# adb.net
KiCad netlist of a schematic drawn in EAGLE
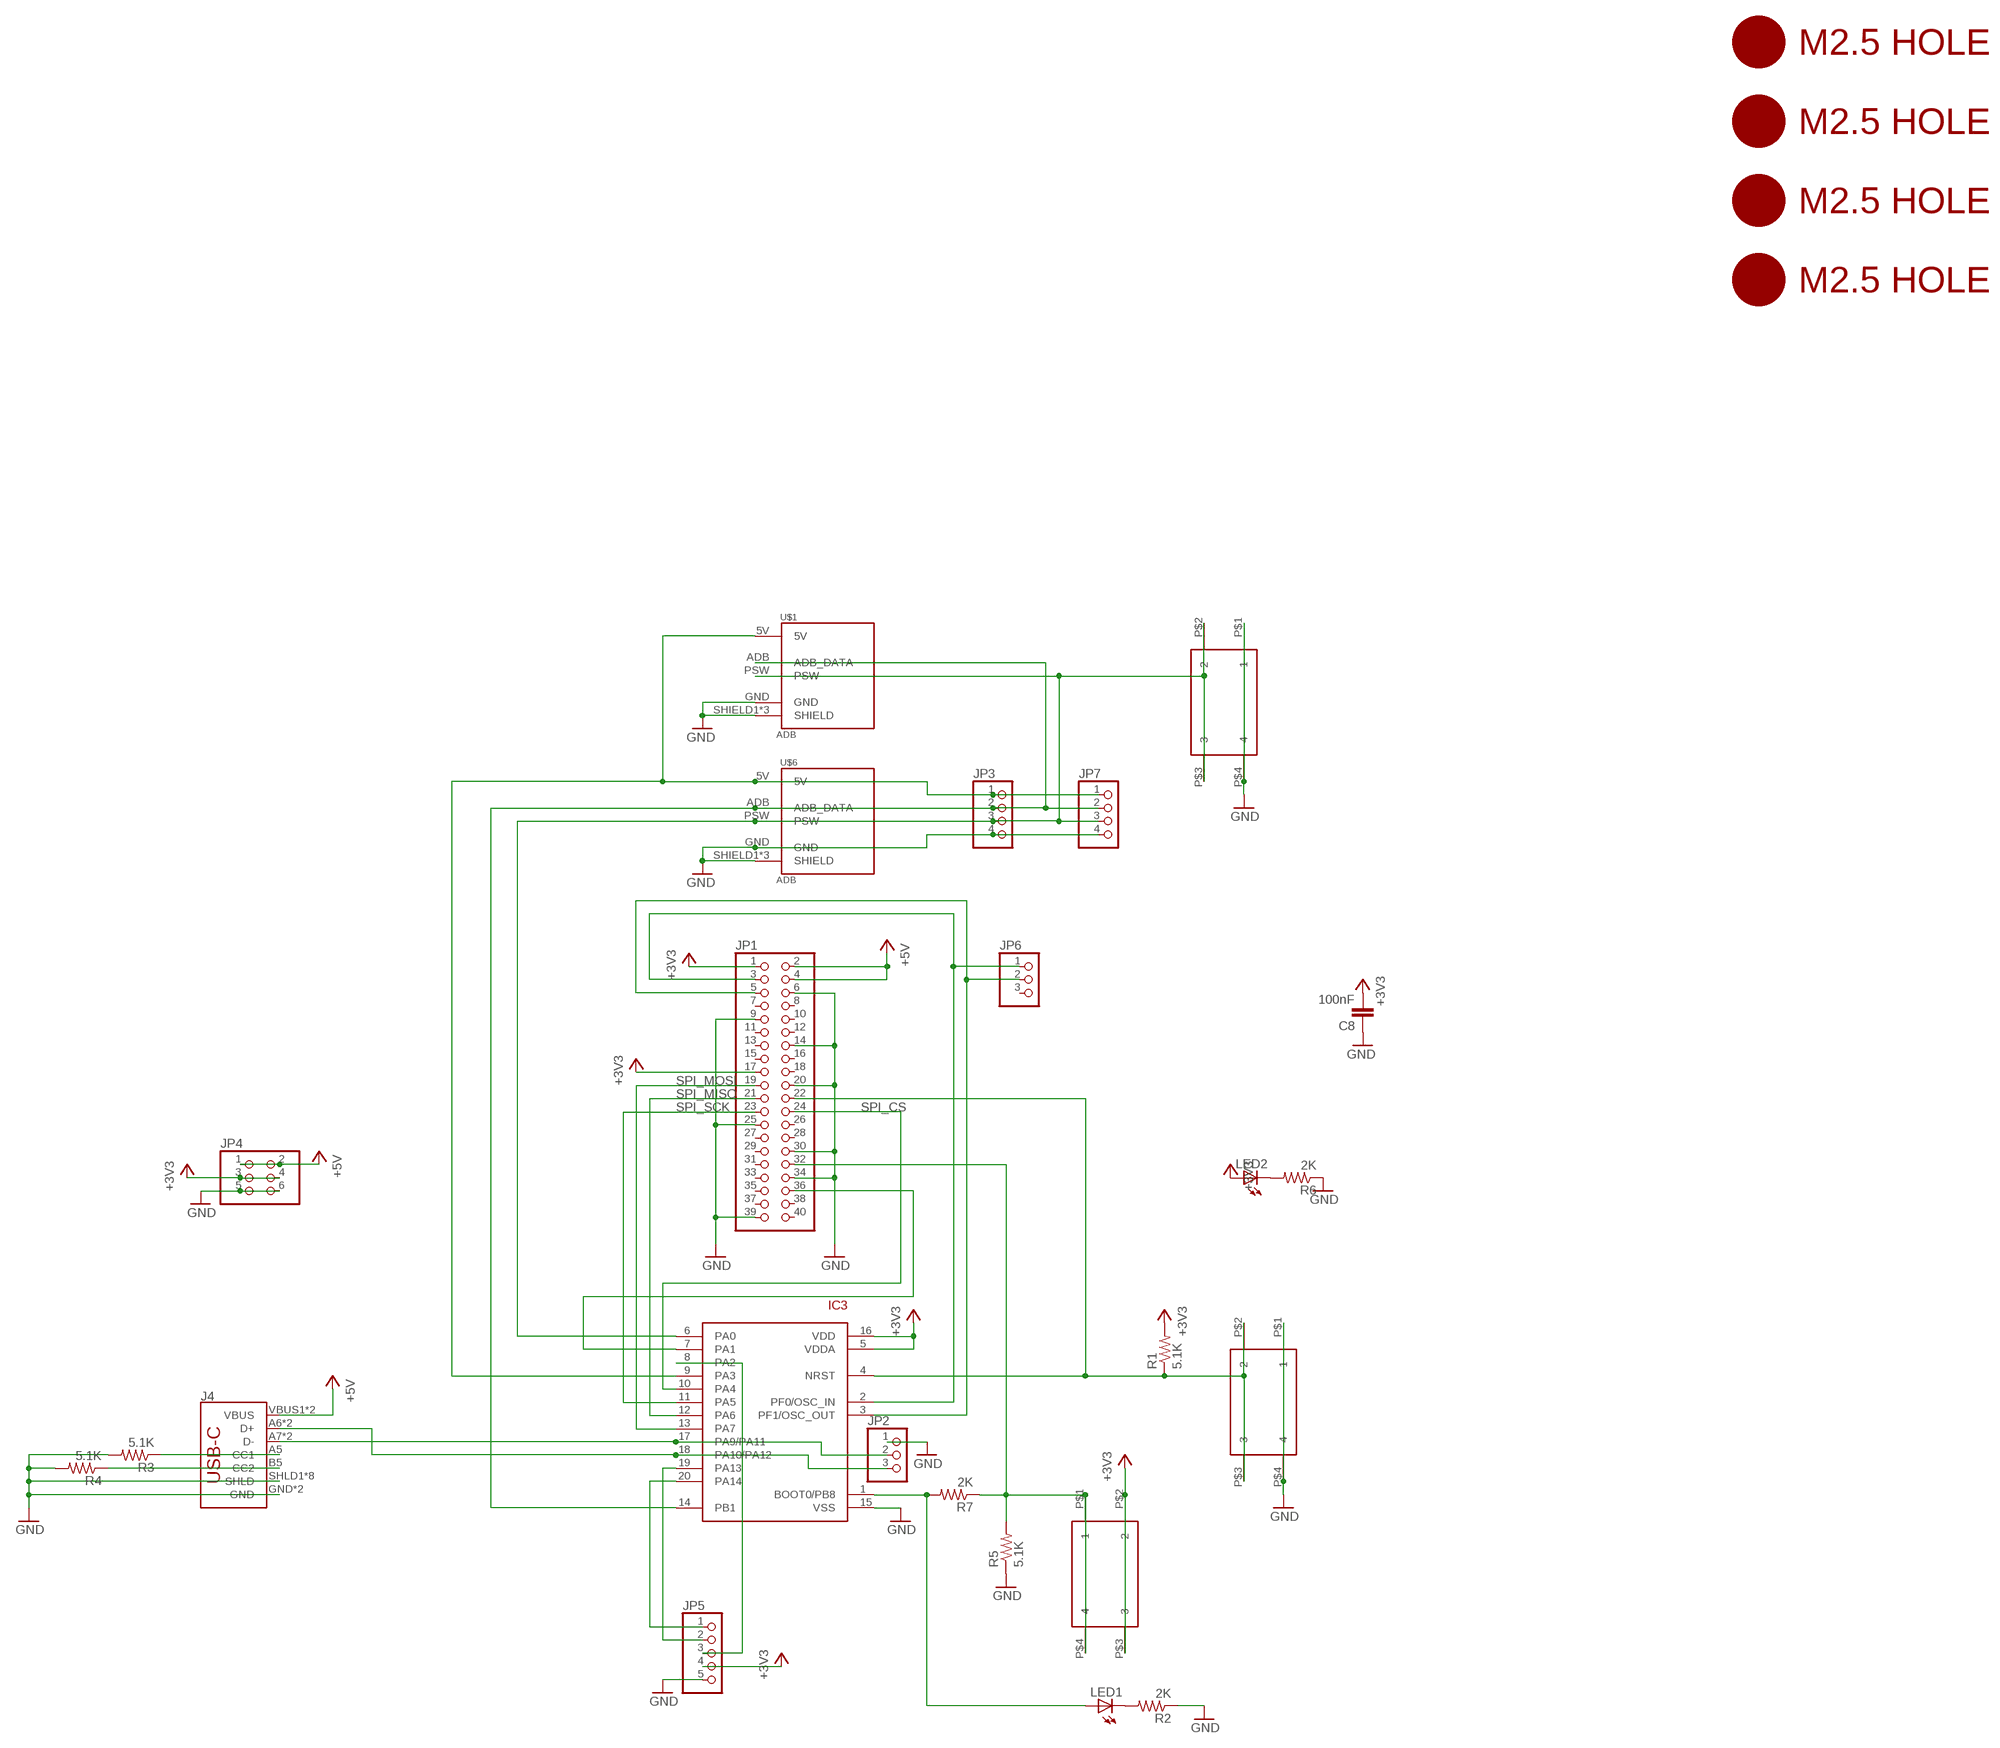
[diagram p0: schematic, sheet 1]

(export (version "E")
  (design (tool "Eeschema 10.0.6"))
  (components
    (comp (ref "C8")
      (value "100nF")
      (footprint "eagle-import:0805@1")
      (libsource (lib "eagle-import") (part "CAP0805"))
    )
    (comp (ref "IC3")
      (value "STM32F042F4")
      (footprint "eagle-import:TSSOP20")
      (libsource (lib "eagle-import") (part "STM32F042F4"))
    )
    (comp (ref "J4")
      (value "USB_C16PIN")
      (footprint "eagle-import:USB-C-16P")
      (libsource (lib "eagle-import") (part "USB_C16PIN"))
    )
    (comp (ref "JP1")
      (value "PINHD-2X20-BIG")
      (footprint "eagle-import:2X20-BIG")
      (libsource (lib "eagle-import") (part "PINHD-2X20-BIG"))
    )
    (comp (ref "JP2")
      (value "PINHD-1X3")
      (footprint "eagle-import:1X03")
      (libsource (lib "eagle-import") (part "PINHD-1X3"))
    )
    (comp (ref "JP3")
      (value "PINHD-1X4")
      (footprint "eagle-import:1X04")
      (libsource (lib "eagle-import") (part "PINHD-1X4"))
    )
    (comp (ref "JP4")
      (value "PINHD-2X3")
      (footprint "eagle-import:2X03")
      (libsource (lib "eagle-import") (part "PINHD-2X3"))
    )
    (comp (ref "JP5")
      (value "PINHD-1X5")
      (footprint "eagle-import:1X05")
      (libsource (lib "eagle-import") (part "PINHD-1X5"))
    )
    (comp (ref "JP6")
      (value "PINHD-1X3")
      (footprint "eagle-import:1X03")
      (libsource (lib "eagle-import") (part "PINHD-1X3"))
    )
    (comp (ref "JP7")
      (value "PINHD-1X4")
      (footprint "eagle-import:1X04")
      (libsource (lib "eagle-import") (part "PINHD-1X4"))
    )
    (comp (ref "LED1")
      (value "LEDCHIP-LED0805")
      (footprint "eagle-import:CHIP-LED0805")
      (libsource (lib "eagle-import") (part "LEDCHIP-LED0805"))
    )
    (comp (ref "LED2")
      (value "LEDCHIP-LED0805")
      (footprint "eagle-import:CHIP-LED0805")
      (libsource (lib "eagle-import") (part "LEDCHIP-LED0805"))
    )
    (comp (ref "R1")
      (value "5.1K")
      (footprint "eagle-import:0805")
      (libsource (lib "eagle-import") (part "RESISTOR0805-RES"))
    )
    (comp (ref "R2")
      (value "2K")
      (footprint "eagle-import:0805")
      (libsource (lib "eagle-import") (part "RESISTOR0805-RES"))
    )
    (comp (ref "R3")
      (value "5.1K")
      (footprint "eagle-import:0805")
      (libsource (lib "eagle-import") (part "RESISTOR0805-RES"))
    )
    (comp (ref "R4")
      (value "5.1K")
      (footprint "eagle-import:0805")
      (libsource (lib "eagle-import") (part "RESISTOR0805-RES"))
    )
    (comp (ref "R5")
      (value "5.1K")
      (footprint "eagle-import:0805")
      (libsource (lib "eagle-import") (part "RESISTOR0805-RES"))
    )
    (comp (ref "R6")
      (value "2K")
      (footprint "eagle-import:0805")
      (libsource (lib "eagle-import") (part "RESISTOR0805-RES"))
    )
    (comp (ref "R7")
      (value "2K")
      (footprint "eagle-import:0805")
      (libsource (lib "eagle-import") (part "RESISTOR0805-RES"))
    )
    (comp (ref "SW1")
      (value "324_SW")
      (footprint "eagle-import:342_SWICH_FOOT")
      (libsource (lib "eagle-import") (part "324_SW"))
    )
    (comp (ref "SW2")
      (value "324_SW")
      (footprint "eagle-import:342_SWICH_FOOT")
      (libsource (lib "eagle-import") (part "324_SW"))
    )
    (comp (ref "SW4")
      (value "324_SW")
      (footprint "eagle-import:342_SWICH_FOOT")
      (libsource (lib "eagle-import") (part "324_SW"))
    )
    (comp (ref "U$1")
      (value "ADB")
      (footprint "eagle-import:DIN4")
      (libsource (lib "eagle-import") (part "ADB"))
    )
    (comp (ref "U$2")
      (value "M2.5HOLE")
      (footprint "eagle-import:M2.5HOLE")
      (libsource (lib "eagle-import") (part "M2.5HOLE"))
    )
    (comp (ref "U$3")
      (value "M2.5HOLE")
      (footprint "eagle-import:M2.5HOLE")
      (libsource (lib "eagle-import") (part "M2.5HOLE"))
    )
    (comp (ref "U$4")
      (value "M2.5HOLE")
      (footprint "eagle-import:M2.5HOLE")
      (libsource (lib "eagle-import") (part "M2.5HOLE"))
    )
    (comp (ref "U$5")
      (value "M2.5HOLE")
      (footprint "eagle-import:M2.5HOLE")
      (libsource (lib "eagle-import") (part "M2.5HOLE"))
    )
    (comp (ref "U$6")
      (value "ADB")
      (footprint "eagle-import:DIN4")
      (libsource (lib "eagle-import") (part "ADB"))
    )
  )
  (nets
    (net (code "1") (name "+3V3") (class "Default")
      (node (ref "C8") (pin "2") (pinfunction "2_2") (pintype "passive"))
      (node (ref "IC3") (pin "16") (pinfunction "VDD_16") (pintype "bidirectional"))
      (node (ref "IC3") (pin "5") (pinfunction "VDDA_5") (pintype "bidirectional"))
      (node (ref "JP1") (pin "1") (pinfunction "1_1") (pintype "passive"))
      (node (ref "JP1") (pin "17") (pinfunction "17_17") (pintype "passive"))
      (node (ref "JP4") (pin "3") (pinfunction "3_3") (pintype "passive"))
      (node (ref "JP4") (pin "4") (pinfunction "4_4") (pintype "passive"))
      (node (ref "JP5") (pin "4") (pinfunction "4_4") (pintype "passive"))
      (node (ref "LED2") (pin "A") (pinfunction "A_A") (pintype "passive"))
      (node (ref "R1") (pin "2") (pinfunction "2_2") (pintype "passive"))
      (node (ref "SW1") (pin "P$2") (pinfunction "2_P$2") (pintype "bidirectional"))
      (node (ref "SW1") (pin "P$3") (pinfunction "3_P$3") (pintype "bidirectional"))
    )
    (net (code "2") (name "+5V") (class "Default")
      (node (ref "J4") (pin "VBUS1") (pinfunction "VBUS_VBUS1") (pintype "bidirectional"))
      (node (ref "J4") (pin "VBUS2") (pinfunction "VBUS_VBUS2") (pintype "bidirectional"))
      (node (ref "JP1") (pin "2") (pinfunction "2_2") (pintype "passive"))
      (node (ref "JP1") (pin "4") (pinfunction "4_4") (pintype "passive"))
      (node (ref "JP4") (pin "1") (pinfunction "1_1") (pintype "passive"))
      (node (ref "JP4") (pin "2") (pinfunction "2_2") (pintype "passive"))
    )
    (net (code "3") (name "/SPI_CS") (class "Default")
      (node (ref "IC3") (pin "10") (pinfunction "PA4_10") (pintype "bidirectional"))
      (node (ref "JP1") (pin "24") (pinfunction "24_24") (pintype "passive"))
    )
    (net (code "4") (name "/SPI_MISO") (class "Default")
      (node (ref "IC3") (pin "12") (pinfunction "PA6_12") (pintype "bidirectional"))
      (node (ref "JP1") (pin "21") (pinfunction "21_21") (pintype "passive"))
    )
    (net (code "5") (name "/SPI_MOSI") (class "Default")
      (node (ref "IC3") (pin "13") (pinfunction "PA7_13") (pintype "bidirectional"))
      (node (ref "JP1") (pin "19") (pinfunction "19_19") (pintype "passive"))
    )
    (net (code "6") (name "/SPI_SCK") (class "Default")
      (node (ref "IC3") (pin "11") (pinfunction "PA5_11") (pintype "bidirectional"))
      (node (ref "JP1") (pin "23") (pinfunction "23_23") (pintype "passive"))
    )
    (net (code "7") (name "GND") (class "Default")
      (node (ref "C8") (pin "1") (pinfunction "1_1") (pintype "passive"))
      (node (ref "IC3") (pin "15") (pinfunction "VSS_15") (pintype "bidirectional"))
      (node (ref "J4") (pin "GND") (pinfunction "GND_GND") (pintype "bidirectional"))
      (node (ref "J4") (pin "GND2") (pinfunction "GND_GND2") (pintype "bidirectional"))
      (node (ref "J4") (pin "SHLD1") (pinfunction "SHLD_SHLD1") (pintype "bidirectional"))
      (node (ref "J4") (pin "SHLD2") (pinfunction "SHLD_SHLD2") (pintype "bidirectional"))
      (node (ref "J4") (pin "SHLD3") (pinfunction "SHLD_SHLD3") (pintype "bidirectional"))
      (node (ref "J4") (pin "SHLD4") (pinfunction "SHLD_SHLD4") (pintype "bidirectional"))
      (node (ref "J4") (pin "SHLD5") (pinfunction "SHLD_SHLD5") (pintype "bidirectional"))
      (node (ref "J4") (pin "SHLD6") (pinfunction "SHLD_SHLD6") (pintype "bidirectional"))
      (node (ref "J4") (pin "SHLD7") (pinfunction "SHLD_SHLD7") (pintype "bidirectional"))
      (node (ref "J4") (pin "SHLD8") (pinfunction "SHLD_SHLD8") (pintype "bidirectional"))
      (node (ref "JP1") (pin "14") (pinfunction "14_14") (pintype "passive"))
      (node (ref "JP1") (pin "20") (pinfunction "20_20") (pintype "passive"))
      (node (ref "JP1") (pin "25") (pinfunction "25_25") (pintype "passive"))
      (node (ref "JP1") (pin "30") (pinfunction "30_30") (pintype "passive"))
      (node (ref "JP1") (pin "34") (pinfunction "34_34") (pintype "passive"))
      (node (ref "JP1") (pin "39") (pinfunction "39_39") (pintype "passive"))
      (node (ref "JP1") (pin "6") (pinfunction "6_6") (pintype "passive"))
      (node (ref "JP1") (pin "9") (pinfunction "9_9") (pintype "passive"))
      (node (ref "JP2") (pin "1") (pinfunction "1_1") (pintype "passive"))
      (node (ref "JP3") (pin "4") (pinfunction "4_4") (pintype "passive"))
      (node (ref "JP4") (pin "5") (pinfunction "5_5") (pintype "passive"))
      (node (ref "JP4") (pin "6") (pinfunction "6_6") (pintype "passive"))
      (node (ref "JP5") (pin "5") (pinfunction "5_5") (pintype "passive"))
      (node (ref "JP7") (pin "4") (pinfunction "4_4") (pintype "passive"))
      (node (ref "R2") (pin "1") (pinfunction "1_1") (pintype "passive"))
      (node (ref "R3") (pin "2") (pinfunction "2_2") (pintype "passive"))
      (node (ref "R4") (pin "2") (pinfunction "2_2") (pintype "passive"))
      (node (ref "R5") (pin "1") (pinfunction "1_1") (pintype "passive"))
      (node (ref "R6") (pin "1") (pinfunction "1_1") (pintype "passive"))
      (node (ref "SW2") (pin "P$1") (pinfunction "1_P$1") (pintype "bidirectional"))
      (node (ref "SW2") (pin "P$4") (pinfunction "4_P$4") (pintype "bidirectional"))
      (node (ref "SW4") (pin "P$1") (pinfunction "1_P$1") (pintype "bidirectional"))
      (node (ref "SW4") (pin "P$4") (pinfunction "4_P$4") (pintype "bidirectional"))
      (node (ref "U$1") (pin "GND") (pinfunction "GND_GND") (pintype "bidirectional"))
      (node (ref "U$1") (pin "SHIELD1") (pinfunction "SHIELD_SHIELD1") (pintype "bidirectional"))
      (node (ref "U$1") (pin "SHIELD2") (pinfunction "SHIELD_SHIELD2") (pintype "bidirectional"))
      (node (ref "U$1") (pin "SHIELD3") (pinfunction "SHIELD_SHIELD3") (pintype "bidirectional"))
      (node (ref "U$6") (pin "GND") (pinfunction "GND_GND") (pintype "bidirectional"))
      (node (ref "U$6") (pin "SHIELD1") (pinfunction "SHIELD_SHIELD1") (pintype "bidirectional"))
      (node (ref "U$6") (pin "SHIELD2") (pinfunction "SHIELD_SHIELD2") (pintype "bidirectional"))
      (node (ref "U$6") (pin "SHIELD3") (pinfunction "SHIELD_SHIELD3") (pintype "bidirectional"))
    )
    (net (code "8") (name "Net-(IC3-BOOT0{slash}PB8)") (class "Default")
      (node (ref "IC3") (pin "1") (pinfunction "BOOT0/PB8_1") (pintype "bidirectional"))
      (node (ref "LED1") (pin "A") (pinfunction "A_A") (pintype "passive"))
      (node (ref "R7") (pin "2") (pinfunction "2_2") (pintype "passive"))
    )
    (net (code "9") (name "Net-(IC3-NRST)") (class "Default")
      (node (ref "IC3") (pin "4") (pinfunction "NRST_4") (pintype "bidirectional"))
      (node (ref "JP1") (pin "22") (pinfunction "22_22") (pintype "passive"))
      (node (ref "R1") (pin "1") (pinfunction "1_1") (pintype "passive"))
      (node (ref "SW4") (pin "P$2") (pinfunction "2_P$2") (pintype "bidirectional"))
      (node (ref "SW4") (pin "P$3") (pinfunction "3_P$3") (pintype "bidirectional"))
    )
    (net (code "10") (name "Net-(IC3-PA0)") (class "Default")
      (node (ref "IC3") (pin "6") (pinfunction "PA0_6") (pintype "bidirectional"))
      (node (ref "JP3") (pin "3") (pinfunction "3_3") (pintype "passive"))
      (node (ref "JP7") (pin "3") (pinfunction "3_3") (pintype "passive"))
      (node (ref "SW2") (pin "P$2") (pinfunction "2_P$2") (pintype "bidirectional"))
      (node (ref "SW2") (pin "P$3") (pinfunction "3_P$3") (pintype "bidirectional"))
      (node (ref "U$1") (pin "PSW") (pinfunction "PSW_PSW") (pintype "bidirectional"))
      (node (ref "U$6") (pin "PSW") (pinfunction "PSW_PSW") (pintype "bidirectional"))
    )
    (net (code "11") (name "Net-(IC3-PA1)") (class "Default")
      (node (ref "IC3") (pin "7") (pinfunction "PA1_7") (pintype "bidirectional"))
      (node (ref "JP1") (pin "36") (pinfunction "36_36") (pintype "passive"))
    )
    (net (code "12") (name "Net-(IC3-PA2)") (class "Default")
      (node (ref "IC3") (pin "8") (pinfunction "PA2_8") (pintype "bidirectional"))
      (node (ref "JP5") (pin "3") (pinfunction "3_3") (pintype "passive"))
    )
    (net (code "13") (name "Net-(IC3-PA3)") (class "Default")
      (node (ref "IC3") (pin "9") (pinfunction "PA3_9") (pintype "bidirectional"))
      (node (ref "JP3") (pin "1") (pinfunction "1_1") (pintype "passive"))
      (node (ref "JP7") (pin "1") (pinfunction "1_1") (pintype "passive"))
      (node (ref "U$1") (pin "5V") (pinfunction "5V_5V") (pintype "bidirectional"))
      (node (ref "U$6") (pin "5V") (pinfunction "5V_5V") (pintype "bidirectional"))
    )
    (net (code "14") (name "Net-(IC3-PA9{slash}PA11)") (class "Default")
      (node (ref "IC3") (pin "17") (pinfunction "PA9/PA11_17") (pintype "bidirectional"))
      (node (ref "J4") (pin "A7") (pinfunction "D-_A7") (pintype "bidirectional"))
      (node (ref "J4") (pin "B7") (pinfunction "D-_B7") (pintype "bidirectional"))
      (node (ref "JP2") (pin "2") (pinfunction "2_2") (pintype "passive"))
    )
    (net (code "15") (name "Net-(IC3-PA10{slash}PA12)") (class "Default")
      (node (ref "IC3") (pin "18") (pinfunction "PA10/PA12_18") (pintype "bidirectional"))
      (node (ref "J4") (pin "A6") (pinfunction "D+_A6") (pintype "bidirectional"))
      (node (ref "J4") (pin "B6") (pinfunction "D+_B6") (pintype "bidirectional"))
      (node (ref "JP2") (pin "3") (pinfunction "3_3") (pintype "passive"))
    )
    (net (code "16") (name "Net-(IC3-PA13)") (class "Default")
      (node (ref "IC3") (pin "19") (pinfunction "PA13_19") (pintype "bidirectional"))
      (node (ref "JP5") (pin "2") (pinfunction "2_2") (pintype "passive"))
    )
    (net (code "17") (name "Net-(IC3-PA14)") (class "Default")
      (node (ref "IC3") (pin "20") (pinfunction "PA14_20") (pintype "bidirectional"))
      (node (ref "JP5") (pin "1") (pinfunction "1_1") (pintype "passive"))
    )
    (net (code "18") (name "Net-(IC3-PB1)") (class "Default")
      (node (ref "IC3") (pin "14") (pinfunction "PB1_14") (pintype "bidirectional"))
      (node (ref "JP3") (pin "2") (pinfunction "2_2") (pintype "passive"))
      (node (ref "JP7") (pin "2") (pinfunction "2_2") (pintype "passive"))
      (node (ref "U$1") (pin "ADB") (pinfunction "ADB_DATA_ADB") (pintype "bidirectional"))
      (node (ref "U$6") (pin "ADB") (pinfunction "ADB_DATA_ADB") (pintype "bidirectional"))
    )
    (net (code "19") (name "Net-(IC3-PF0{slash}OSC_IN)") (class "Default")
      (node (ref "IC3") (pin "2") (pinfunction "PF0/OSC_IN_2") (pintype "bidirectional"))
      (node (ref "JP1") (pin "3") (pinfunction "3_3") (pintype "passive"))
      (node (ref "JP6") (pin "1") (pinfunction "1_1") (pintype "passive"))
    )
    (net (code "20") (name "Net-(IC3-PF1{slash}OSC_OUT)") (class "Default")
      (node (ref "IC3") (pin "3") (pinfunction "PF1/OSC_OUT_3") (pintype "bidirectional"))
      (node (ref "JP1") (pin "5") (pinfunction "5_5") (pintype "passive"))
      (node (ref "JP6") (pin "2") (pinfunction "2_2") (pintype "passive"))
    )
    (net (code "21") (name "Net-(J4-CC1)") (class "Default")
      (node (ref "J4") (pin "A5") (pinfunction "CC1_A5") (pintype "bidirectional"))
      (node (ref "R3") (pin "1") (pinfunction "1_1") (pintype "passive"))
    )
    (net (code "22") (name "Net-(J4-CC2)") (class "Default")
      (node (ref "J4") (pin "B5") (pinfunction "CC2_B5") (pintype "bidirectional"))
      (node (ref "R4") (pin "1") (pinfunction "1_1") (pintype "passive"))
    )
    (net (code "23") (name "Net-(LED1-PadC)") (class "Default")
      (node (ref "LED1") (pin "C") (pinfunction "C_C") (pintype "passive"))
      (node (ref "R2") (pin "2") (pinfunction "2_2") (pintype "passive"))
    )
    (net (code "24") (name "Net-(LED2-PadC)") (class "Default")
      (node (ref "LED2") (pin "C") (pinfunction "C_C") (pintype "passive"))
      (node (ref "R6") (pin "2") (pinfunction "2_2") (pintype "passive"))
    )
    (net (code "25") (name "Net-(SW1-1)") (class "Default")
      (node (ref "JP1") (pin "32") (pinfunction "32_32") (pintype "passive"))
      (node (ref "R5") (pin "2") (pinfunction "2_2") (pintype "passive"))
      (node (ref "R7") (pin "1") (pinfunction "1_1") (pintype "passive"))
      (node (ref "SW1") (pin "P$1") (pinfunction "1_P$1") (pintype "bidirectional"))
      (node (ref "SW1") (pin "P$4") (pinfunction "4_P$4") (pintype "bidirectional"))
    )
    (net (code "26") (name "unconnected-(JP1-Pad7)") (class "Default")
      (node (ref "JP1") (pin "7") (pinfunction "7_7") (pintype "passive"))
    )
    (net (code "27") (name "unconnected-(JP1-Pad8)") (class "Default")
      (node (ref "JP1") (pin "8") (pinfunction "8_8") (pintype "passive"))
    )
    (net (code "28") (name "unconnected-(JP1-Pad10)") (class "Default")
      (node (ref "JP1") (pin "10") (pinfunction "10_10") (pintype "passive"))
    )
    (net (code "29") (name "unconnected-(JP1-Pad11)") (class "Default")
      (node (ref "JP1") (pin "11") (pinfunction "11_11") (pintype "passive"))
    )
    (net (code "30") (name "unconnected-(JP1-Pad12)") (class "Default")
      (node (ref "JP1") (pin "12") (pinfunction "12_12") (pintype "passive"))
    )
    (net (code "31") (name "unconnected-(JP1-Pad13)") (class "Default")
      (node (ref "JP1") (pin "13") (pinfunction "13_13") (pintype "passive"))
    )
    (net (code "32") (name "unconnected-(JP1-Pad15)") (class "Default")
      (node (ref "JP1") (pin "15") (pinfunction "15_15") (pintype "passive"))
    )
    (net (code "33") (name "unconnected-(JP1-Pad16)") (class "Default")
      (node (ref "JP1") (pin "16") (pinfunction "16_16") (pintype "passive"))
    )
    (net (code "34") (name "unconnected-(JP1-Pad18)") (class "Default")
      (node (ref "JP1") (pin "18") (pinfunction "18_18") (pintype "passive"))
    )
    (net (code "35") (name "unconnected-(JP1-Pad26)") (class "Default")
      (node (ref "JP1") (pin "26") (pinfunction "26_26") (pintype "passive"))
    )
    (net (code "36") (name "unconnected-(JP1-Pad27)") (class "Default")
      (node (ref "JP1") (pin "27") (pinfunction "27_27") (pintype "passive"))
    )
    (net (code "37") (name "unconnected-(JP1-Pad28)") (class "Default")
      (node (ref "JP1") (pin "28") (pinfunction "28_28") (pintype "passive"))
    )
    (net (code "38") (name "unconnected-(JP1-Pad29)") (class "Default")
      (node (ref "JP1") (pin "29") (pinfunction "29_29") (pintype "passive"))
    )
    (net (code "39") (name "unconnected-(JP1-Pad31)") (class "Default")
      (node (ref "JP1") (pin "31") (pinfunction "31_31") (pintype "passive"))
    )
    (net (code "40") (name "unconnected-(JP1-Pad33)") (class "Default")
      (node (ref "JP1") (pin "33") (pinfunction "33_33") (pintype "passive"))
    )
    (net (code "41") (name "unconnected-(JP1-Pad35)") (class "Default")
      (node (ref "JP1") (pin "35") (pinfunction "35_35") (pintype "passive"))
    )
    (net (code "42") (name "unconnected-(JP1-Pad37)") (class "Default")
      (node (ref "JP1") (pin "37") (pinfunction "37_37") (pintype "passive"))
    )
    (net (code "43") (name "unconnected-(JP1-Pad38)") (class "Default")
      (node (ref "JP1") (pin "38") (pinfunction "38_38") (pintype "passive"))
    )
    (net (code "44") (name "unconnected-(JP1-Pad40)") (class "Default")
      (node (ref "JP1") (pin "40") (pinfunction "40_40") (pintype "passive"))
    )
    (net (code "45") (name "unconnected-(JP6-Pad3)") (class "Default")
      (node (ref "JP6") (pin "3") (pinfunction "3_3") (pintype "passive"))
    )
  )
)
